# PDM-S03-V00-PSU.net
KiCad netlist of a schematic drawn in Altium Designer
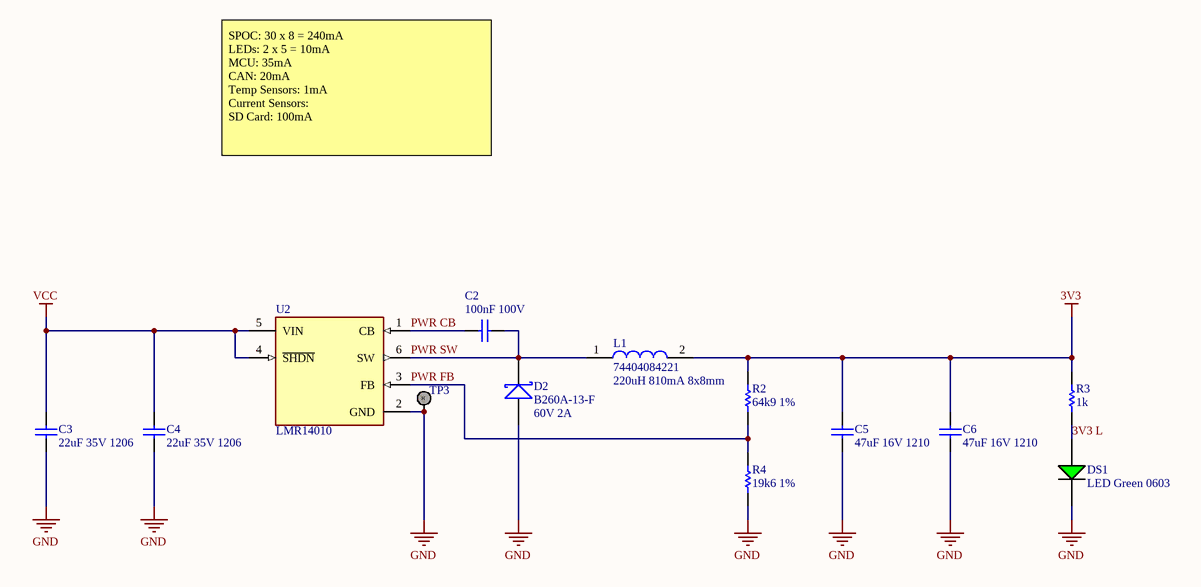
[diagram p0: PDM-S03-V00-PSU.SchDoc]

(export (version "E")
  (design (tool "Eeschema 10.0.6"))
  (components
    (comp (ref "C2")
      (value "100nF 100V")
      (footprint "Cap_Ceramic_0603")
      (description "Capacitor, Ceramic, SMD, 100nF, 100V, 5%, X7R, 0603")
      (libsource (lib "StandardCapacitors") (part "100nF 100V 5% X7R 0603"))
    )
    (comp (ref "C3")
      (value "22uF 35V 1206")
      (footprint "Cap_Ceramic_1206")
      (description "Capacitor, Ceramic, SMD, 22uF, 35V, 10%, X7R, 1206")
      (libsource (lib "StandardCapacitors") (part "22uF 35V 10% X7R 1206"))
    )
    (comp (ref "C4")
      (value "22uF 35V 1206")
      (footprint "Cap_Ceramic_1206")
      (description "Capacitor, Ceramic, SMD, 22uF, 35V, 10%, X7R, 1206")
      (libsource (lib "StandardCapacitors") (part "22uF 35V 10% X7R 1206"))
    )
    (comp (ref "C5")
      (value "47uF 16V 1210")
      (footprint "Cap_Ceramic_1210")
      (description "Capacitor, Ceramic, SMD, 47uF, 16V, 5%, X7R, 1210")
      (libsource (lib "StandardCapacitors") (part "47uF 16V 10% X7R 1210"))
    )
    (comp (ref "C6")
      (value "47uF 16V 1210")
      (footprint "Cap_Ceramic_1210")
      (description "Capacitor, Ceramic, SMD, 47uF, 16V, 5%, X7R, 1210")
      (libsource (lib "StandardCapacitors") (part "47uF 16V 10% X7R 1210"))
    )
    (comp (ref "D2")
      (value "B260A-13-F")
      (footprint "SMA")
      (description "Diode, Schottky Barrier Rectifier, 60 V, 2 A, B260A-13-F")
      (libsource (lib "QUTMS_DiodeLibrary") (part "B260A-13-F"))
    )
    (comp (ref "DS1")
      (value "LED Green 0603")
      (footprint "LED GREEN 0603")
      (libsource (lib "QUTMS_LEDLibrary") (part "LED Green 0603"))
    )
    (comp (ref "L1")
      (value "74404084221")
      (footprint "Inductor_8x8mm")
      (description "FIXED IND 220UH 810MA 592 MOHM")
      (libsource (lib "QUTMS_InductorLibrary") (part "74404084221"))
    )
    (comp (ref "R2")
      (value "64k9 1%")
      (footprint "Res_ThinFilm_0603")
      (description "Resistor, SMD, 64k9, 0.1W, 5%, 0603")
      (libsource (lib "StandardResistors") (part "64k9 1% 0603"))
    )
    (comp (ref "R3")
      (value "1k")
      (footprint "Res_ThinFilm_0603")
      (description "Resistor, SMD, 1k, 0.1W, 5%, 0603")
      (libsource (lib "StandardResistors") (part "1k 5% 0603"))
    )
    (comp (ref "R4")
      (value "19k6 1%")
      (footprint "Res_ThinFilm_0603")
      (description "Resistor, SMD, 19k6, 0.1W, 5%, 0603")
      (libsource (lib "StandardResistors") (part "19k6 1% 0603"))
    )
    (comp (ref "TP3")
      (value "TestPoint_Hoop_Black")
      (footprint "TestPointHoop_BLACK")
      (libsource (lib "StandardTest") (part "TestPoint_Hoop_Black"))
    )
    (comp (ref "U2")
      (value "LMR14010")
      (footprint "LMR14010")
      (libsource (lib "QUTMS_PowerSupplyLibrary") (part "LMR14010"))
    )
  )
  (nets
    (net (code "1") (name "/3V3 L") (class "Default")
      (node (ref "DS1") (pin "1") (pinfunction "A_1") (pintype "passive"))
      (node (ref "R3") (pin "1") (pinfunction "1_1") (pintype "passive"))
    )
    (net (code "2") (name "/PWR CB") (class "Default")
      (node (ref "C2") (pin "1") (pinfunction "1_1") (pintype "passive"))
      (node (ref "U2") (pin "1") (pinfunction "CB_1") (pintype "input"))
    )
    (net (code "3") (name "/PWR FB") (class "Default")
      (node (ref "R2") (pin "1") (pinfunction "1_1") (pintype "passive"))
      (node (ref "R4") (pin "2") (pinfunction "2_2") (pintype "passive"))
      (node (ref "U2") (pin "3") (pinfunction "FB_3") (pintype "input"))
    )
    (net (code "4") (name "/PWR SW") (class "Default")
      (node (ref "C2") (pin "2") (pinfunction "2_2") (pintype "passive"))
      (node (ref "D2") (pin "K") (pinfunction "K_K") (pintype "passive"))
      (node (ref "L1") (pin "1") (pinfunction "1_1") (pintype "passive"))
      (node (ref "U2") (pin "6") (pinfunction "SW_6") (pintype "output"))
    )
    (net (code "5") (name "3V3") (class "Default")
      (node (ref "C5") (pin "2") (pinfunction "2_2") (pintype "passive"))
      (node (ref "C6") (pin "2") (pinfunction "2_2") (pintype "passive"))
      (node (ref "L1") (pin "2") (pinfunction "2_2") (pintype "passive"))
      (node (ref "R2") (pin "2") (pinfunction "2_2") (pintype "passive"))
      (node (ref "R3") (pin "2") (pinfunction "2_2") (pintype "passive"))
    )
    (net (code "6") (name "GND") (class "Default")
      (node (ref "C3") (pin "1") (pinfunction "1_1") (pintype "passive"))
      (node (ref "C4") (pin "1") (pinfunction "1_1") (pintype "passive"))
      (node (ref "C5") (pin "1") (pinfunction "1_1") (pintype "passive"))
      (node (ref "C6") (pin "1") (pinfunction "1_1") (pintype "passive"))
      (node (ref "D2") (pin "A") (pinfunction "A_A") (pintype "passive"))
      (node (ref "DS1") (pin "2") (pinfunction "C_2") (pintype "passive"))
      (node (ref "R4") (pin "1") (pinfunction "1_1") (pintype "passive"))
      (node (ref "TP3") (pin "1") (pinfunction "1_1") (pintype "passive"))
      (node (ref "U2") (pin "2") (pinfunction "GND_2") (pintype "power_in"))
    )
    (net (code "7") (name "VCC") (class "Default")
      (node (ref "C3") (pin "2") (pinfunction "2_2") (pintype "passive"))
      (node (ref "C4") (pin "2") (pinfunction "2_2") (pintype "passive"))
      (node (ref "U2") (pin "4") (pinfunction "~{SHDN}_4") (pintype "input"))
      (node (ref "U2") (pin "5") (pinfunction "VIN_5") (pintype "power_in"))
    )
  )
)
